# Sheet1.net
KiCad netlist of a schematic drawn in Altium Designer
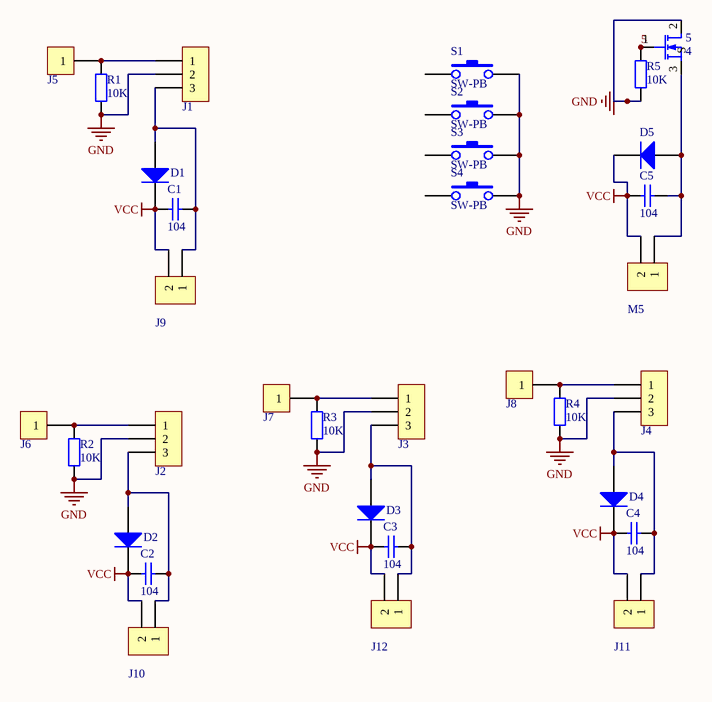
[diagram p0: Sheet1.SchDoc]

(export (version "E")
  (design (tool "Eeschema 10.0.6"))
  (components
    (comp (ref "5")
      (value "4")
      (footprint "SOT-23")
      (description "N-MOSFET")
      (libsource (lib "GBY的原理图库") (part "IRF840"))
    )
    (comp (ref "C1")
      (value "104")
      (footprint "C0805")
      (description "Capacitor")
      (fields (field (name "PUBLISHER") "Altium Limited"))
      (libsource (lib "Miscellaneous Devices") (part "Cap"))
    )
    (comp (ref "C2")
      (value "104")
      (footprint "C0805")
      (description "Capacitor")
      (fields (field (name "PUBLISHER") "Altium Limited"))
      (libsource (lib "Miscellaneous Devices") (part "Cap"))
    )
    (comp (ref "C3")
      (value "104")
      (footprint "C0805")
      (description "Capacitor")
      (fields (field (name "PUBLISHER") "Altium Limited"))
      (libsource (lib "Miscellaneous Devices") (part "Cap"))
    )
    (comp (ref "C4")
      (value "104")
      (footprint "C0805")
      (description "Capacitor")
      (fields (field (name "PUBLISHER") "Altium Limited"))
      (libsource (lib "Miscellaneous Devices") (part "Cap"))
    )
    (comp (ref "C5")
      (value "104")
      (footprint "0805")
      (description "Capacitor")
      (fields (field (name "PUBLISHER") "Altium Limited"))
      (libsource (lib "Miscellaneous Devices") (part "Cap"))
    )
    (comp (ref "D1")
      (value "Diode 1N4007")
      (footprint "0805D")
      (description "1 Amp General Purpose Rectifier")
      (fields (field (name "PUBLISHER") "Altium Limited"))
      (libsource (lib "Miscellaneous Devices") (part "Diode 1N4007"))
    )
    (comp (ref "D2")
      (value "Diode 1N4007")
      (footprint "0805D")
      (description "1 Amp General Purpose Rectifier")
      (fields (field (name "PUBLISHER") "Altium Limited"))
      (libsource (lib "Miscellaneous Devices") (part "Diode 1N4007"))
    )
    (comp (ref "D3")
      (value "Diode 1N4007")
      (footprint "0805D")
      (description "1 Amp General Purpose Rectifier")
      (fields (field (name "PUBLISHER") "Altium Limited"))
      (libsource (lib "Miscellaneous Devices") (part "Diode 1N4007"))
    )
    (comp (ref "D4")
      (value "Diode 1N4007")
      (footprint "0805D")
      (description "1 Amp General Purpose Rectifier")
      (fields (field (name "PUBLISHER") "Altium Limited"))
      (libsource (lib "Miscellaneous Devices") (part "Diode 1N4007"))
    )
    (comp (ref "D5")
      (value "Diode 1N4007")
      (footprint "0805D")
      (description "1 Amp General Purpose Rectifier")
      (fields (field (name "PUBLISHER") "Altium Limited"))
      (libsource (lib "Miscellaneous Devices") (part "Diode 1N4007"))
    )
    (comp (ref "J1") (value "mos") (footprint "SOT-23") (libsource (lib "常用元件库") (part "CON3")))
    (comp (ref "J2") (value "mos") (footprint "SOT-23") (libsource (lib "常用元件库") (part "CON3")))
    (comp (ref "J3") (value "mos") (footprint "SOT-23") (libsource (lib "常用元件库") (part "CON3")))
    (comp (ref "J4") (value "mos") (footprint "SOT-23") (libsource (lib "常用元件库") (part "CON3")))
    (comp (ref "J5") (value "CON1") (footprint "DG1281-5.0") (libsource (lib "常用元件库") (part "CON1")))
    (comp (ref "J6") (value "CON1") (footprint "DG1281-5.0") (libsource (lib "常用元件库") (part "CON1")))
    (comp (ref "J7") (value "CON1") (footprint "DG1281-5.0") (libsource (lib "常用元件库") (part "CON1")))
    (comp (ref "J8") (value "CON1") (footprint "DG1281-5.0") (libsource (lib "常用元件库") (part "CON1")))
    (comp (ref "J9") (value "CON2") (footprint "zdy:PCBComponent_1") (libsource (lib "常用元件库") (part "CON2")))
    (comp (ref "J10") (value "CON2") (footprint "zdy:PCBComponent_1") (libsource (lib "常用元件库") (part "CON2")))
    (comp (ref "J11") (value "CON2") (footprint "zdy:PCBComponent_1") (libsource (lib "常用元件库") (part "CON2")))
    (comp (ref "J12") (value "CON2") (footprint "zdy:PCBComponent_1") (libsource (lib "常用元件库") (part "CON2")))
    (comp (ref "M5") (value "CON2") (footprint "SIP2") (libsource (lib "原理图封装库") (part "CON2")))
    (comp (ref "R1")
      (value "10K")
      (footprint "0805")
      (description "Resistor")
      (fields (field (name "Comment") "Res2") (field (name "PUBLISHER") "Altium Limited"))
      (libsource (lib "Miscellaneous Devices") (part "Res2"))
    )
    (comp (ref "R2")
      (value "10K")
      (footprint "0805")
      (description "Resistor")
      (fields (field (name "Comment") "Res2") (field (name "PUBLISHER") "Altium Limited"))
      (libsource (lib "Miscellaneous Devices") (part "Res2"))
    )
    (comp (ref "R3")
      (value "10K")
      (footprint "0805")
      (description "Resistor")
      (fields (field (name "Comment") "Res2") (field (name "PUBLISHER") "Altium Limited"))
      (libsource (lib "Miscellaneous Devices") (part "Res2"))
    )
    (comp (ref "R4")
      (value "10K")
      (footprint "0805")
      (description "Resistor")
      (fields (field (name "Comment") "Res2") (field (name "PUBLISHER") "Altium Limited"))
      (libsource (lib "Miscellaneous Devices") (part "Res2"))
    )
    (comp (ref "R5")
      (value "10K")
      (footprint "0805")
      (description "Resistor")
      (fields (field (name "Comment") "Res2") (field (name "PUBLISHER") "Altium Limited"))
      (libsource (lib "Miscellaneous Devices") (part "Res2"))
    )
    (comp (ref "S1") (value "SW-PB") (footprint "AXIAL0.3") (libsource (lib "杂元件库") (part "SW-PB")))
    (comp (ref "S2") (value "SW-PB") (footprint "AXIAL0.3") (libsource (lib "杂元件库") (part "SW-PB")))
    (comp (ref "S3") (value "SW-PB") (footprint "AXIAL0.3") (libsource (lib "杂元件库") (part "SW-PB")))
    (comp (ref "S4") (value "SW-PB") (footprint "AXIAL0.3") (libsource (lib "杂元件库") (part "SW-PB")))
  )
  (nets
    (net (code "1") (name "/5") (class "Default")
      (node (ref "5") (pin "1") (pinfunction "G_1") (pintype "passive"))
      (node (ref "R5") (pin "2") (pinfunction "2_2") (pintype "passive"))
    )
    (net (code "2") (name "GND") (class "Default")
      (node (ref "5") (pin "2") (pinfunction "D_2") (pintype "passive"))
      (node (ref "J1") (pin "2") (pinfunction "2_2") (pintype "passive"))
      (node (ref "J2") (pin "2") (pinfunction "2_2") (pintype "passive"))
      (node (ref "J3") (pin "2") (pinfunction "2_2") (pintype "passive"))
      (node (ref "J4") (pin "2") (pinfunction "2_2") (pintype "passive"))
      (node (ref "R1") (pin "1") (pinfunction "1_1") (pintype "passive"))
      (node (ref "R2") (pin "1") (pinfunction "1_1") (pintype "passive"))
      (node (ref "R3") (pin "1") (pinfunction "1_1") (pintype "passive"))
      (node (ref "R4") (pin "1") (pinfunction "1_1") (pintype "passive"))
      (node (ref "R5") (pin "1") (pinfunction "1_1") (pintype "passive"))
      (node (ref "S1") (pin "2") (pinfunction "2_2") (pintype "passive"))
      (node (ref "S2") (pin "2") (pinfunction "2_2") (pintype "passive"))
      (node (ref "S3") (pin "2") (pinfunction "2_2") (pintype "passive"))
      (node (ref "S4") (pin "2") (pinfunction "2_2") (pintype "passive"))
    )
    (net (code "3") (name "Net-(5-S)") (class "Default")
      (node (ref "5") (pin "3") (pinfunction "S_3") (pintype "passive"))
      (node (ref "C5") (pin "2") (pinfunction "2_2") (pintype "passive"))
      (node (ref "D5") (pin "1") (pinfunction "A_1") (pintype "passive"))
      (node (ref "M5") (pin "1") (pinfunction "1_1") (pintype "passive"))
    )
    (net (code "4") (name "Net-(D1-A)") (class "Default")
      (node (ref "C1") (pin "2") (pinfunction "2_2") (pintype "passive"))
      (node (ref "D1") (pin "1") (pinfunction "A_1") (pintype "passive"))
      (node (ref "J1") (pin "3") (pinfunction "3_3") (pintype "passive"))
      (node (ref "J9") (pin "1") (pinfunction "1_1") (pintype "passive"))
    )
    (net (code "5") (name "Net-(D2-A)") (class "Default")
      (node (ref "C2") (pin "2") (pinfunction "2_2") (pintype "passive"))
      (node (ref "D2") (pin "1") (pinfunction "A_1") (pintype "passive"))
      (node (ref "J10") (pin "1") (pinfunction "1_1") (pintype "passive"))
      (node (ref "J2") (pin "3") (pinfunction "3_3") (pintype "passive"))
    )
    (net (code "6") (name "Net-(D3-A)") (class "Default")
      (node (ref "C3") (pin "2") (pinfunction "2_2") (pintype "passive"))
      (node (ref "D3") (pin "1") (pinfunction "A_1") (pintype "passive"))
      (node (ref "J12") (pin "1") (pinfunction "1_1") (pintype "passive"))
      (node (ref "J3") (pin "3") (pinfunction "3_3") (pintype "passive"))
    )
    (net (code "7") (name "Net-(D4-A)") (class "Default")
      (node (ref "C4") (pin "2") (pinfunction "2_2") (pintype "passive"))
      (node (ref "D4") (pin "1") (pinfunction "A_1") (pintype "passive"))
      (node (ref "J11") (pin "1") (pinfunction "1_1") (pintype "passive"))
      (node (ref "J4") (pin "3") (pinfunction "3_3") (pintype "passive"))
    )
    (net (code "8") (name "Net-(J1-Pad1)") (class "Default")
      (node (ref "J1") (pin "1") (pinfunction "1_1") (pintype "passive"))
      (node (ref "J5") (pin "1") (pinfunction "1_1") (pintype "passive"))
      (node (ref "R1") (pin "2") (pinfunction "2_2") (pintype "passive"))
    )
    (net (code "9") (name "Net-(J2-Pad1)") (class "Default")
      (node (ref "J2") (pin "1") (pinfunction "1_1") (pintype "passive"))
      (node (ref "J6") (pin "1") (pinfunction "1_1") (pintype "passive"))
      (node (ref "R2") (pin "2") (pinfunction "2_2") (pintype "passive"))
    )
    (net (code "10") (name "Net-(J3-Pad1)") (class "Default")
      (node (ref "J3") (pin "1") (pinfunction "1_1") (pintype "passive"))
      (node (ref "J7") (pin "1") (pinfunction "1_1") (pintype "passive"))
      (node (ref "R3") (pin "2") (pinfunction "2_2") (pintype "passive"))
    )
    (net (code "11") (name "Net-(J4-Pad1)") (class "Default")
      (node (ref "J4") (pin "1") (pinfunction "1_1") (pintype "passive"))
      (node (ref "J8") (pin "1") (pinfunction "1_1") (pintype "passive"))
      (node (ref "R4") (pin "2") (pinfunction "2_2") (pintype "passive"))
    )
    (net (code "12") (name "VCC") (class "Default")
      (node (ref "C1") (pin "1") (pinfunction "1_1") (pintype "passive"))
      (node (ref "C2") (pin "1") (pinfunction "1_1") (pintype "passive"))
      (node (ref "C3") (pin "1") (pinfunction "1_1") (pintype "passive"))
      (node (ref "C4") (pin "1") (pinfunction "1_1") (pintype "passive"))
      (node (ref "C5") (pin "1") (pinfunction "1_1") (pintype "passive"))
      (node (ref "D1") (pin "2") (pinfunction "K_2") (pintype "passive"))
      (node (ref "D2") (pin "2") (pinfunction "K_2") (pintype "passive"))
      (node (ref "D3") (pin "2") (pinfunction "K_2") (pintype "passive"))
      (node (ref "D4") (pin "2") (pinfunction "K_2") (pintype "passive"))
      (node (ref "D5") (pin "2") (pinfunction "K_2") (pintype "passive"))
      (node (ref "J10") (pin "2") (pinfunction "2_2") (pintype "passive"))
      (node (ref "J11") (pin "2") (pinfunction "2_2") (pintype "passive"))
      (node (ref "J12") (pin "2") (pinfunction "2_2") (pintype "passive"))
      (node (ref "J9") (pin "2") (pinfunction "2_2") (pintype "passive"))
      (node (ref "M5") (pin "2") (pinfunction "2_2") (pintype "passive"))
    )
    (net (code "13") (name "unconnected-(S1-Pad1)") (class "Default")
      (node (ref "S1") (pin "1") (pinfunction "1_1") (pintype "passive"))
    )
    (net (code "14") (name "unconnected-(S2-Pad1)") (class "Default")
      (node (ref "S2") (pin "1") (pinfunction "1_1") (pintype "passive"))
    )
    (net (code "15") (name "unconnected-(S3-Pad1)") (class "Default")
      (node (ref "S3") (pin "1") (pinfunction "1_1") (pintype "passive"))
    )
    (net (code "16") (name "unconnected-(S4-Pad1)") (class "Default")
      (node (ref "S4") (pin "1") (pinfunction "1_1") (pintype "passive"))
    )
  )
)
